# Power_grad.net
KiCad netlist of a schematic drawn in EAGLE
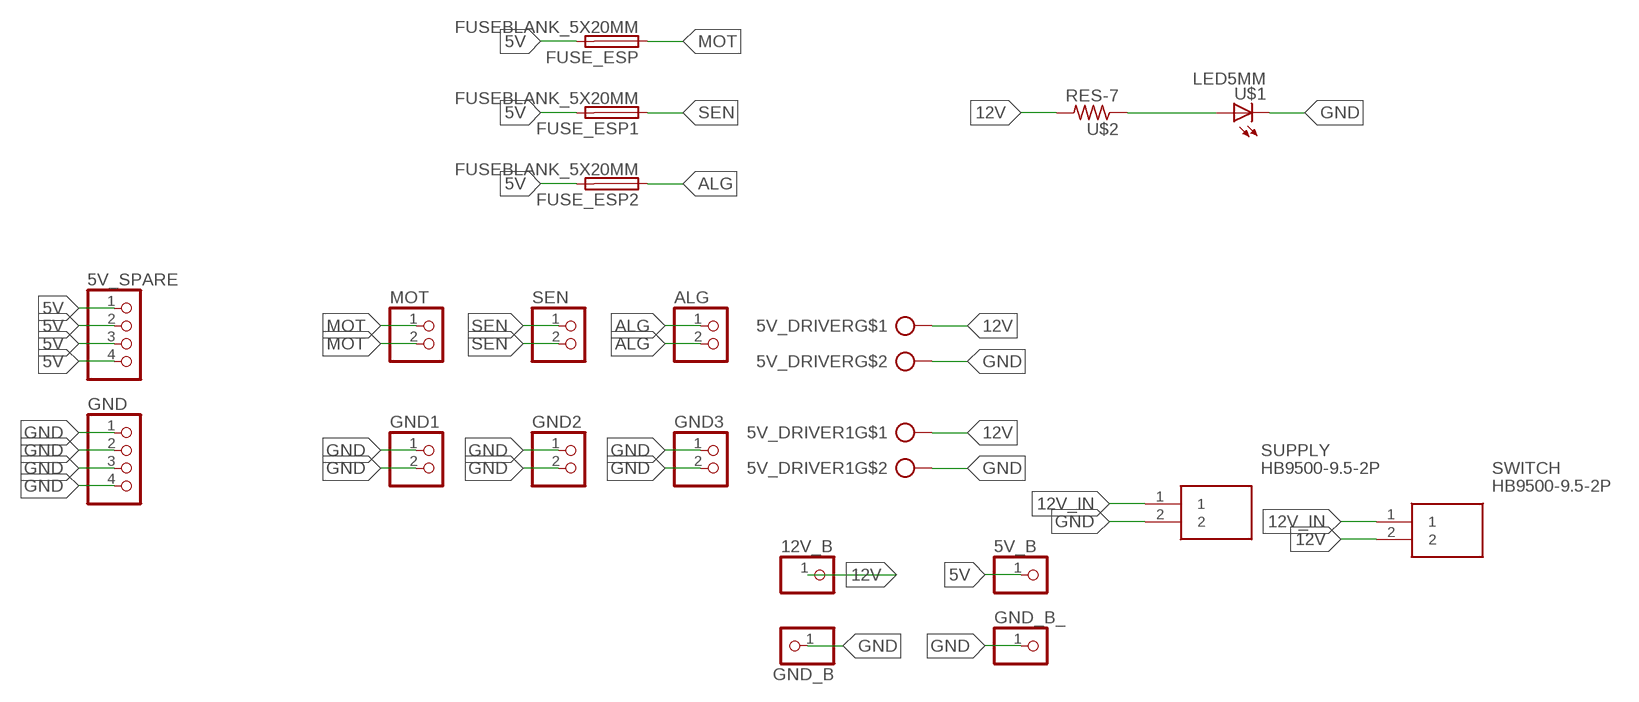
[diagram p0: schematic, sheet 1]

(export (version "E")
  (design (tool "Eeschema 10.0.6"))
  (components
    (comp (ref "5V_B")
      (value "PINHD-1X1")
      (footprint "eagle-import:1X01")
      (libsource (lib "eagle-import") (part "PINHD-1X1"))
    )
    (comp (ref "5V_DRIVER")
      (value "CON_PTR_2")
      (footprint "eagle-import:AK300_2")
      (libsource (lib "eagle-import") (part "CON_PTR_2"))
    )
    (comp (ref "5V_DRIVER1")
      (value "CON_PTR_2")
      (footprint "eagle-import:AK300_2")
      (libsource (lib "eagle-import") (part "CON_PTR_2"))
    )
    (comp (ref "5V_SPARE")
      (value "PINHD-1X4")
      (footprint "eagle-import:1X04")
      (libsource (lib "eagle-import") (part "PINHD-1X4"))
    )
    (comp (ref "12V_B")
      (value "PINHD-1X1")
      (footprint "eagle-import:1X01")
      (libsource (lib "eagle-import") (part "PINHD-1X1"))
    )
    (comp (ref "ALG")
      (value "PINHD-2_DATA")
      (footprint "eagle-import:1X02_DATA")
      (libsource (lib "eagle-import") (part "PINHD-2_DATA"))
    )
    (comp (ref "FUSE_ESP")
      (value "FUSEBLANK_5X20MM")
      (footprint "eagle-import:FUSE_HOLDER_5X20MM")
      (libsource (lib "eagle-import") (part "FUSEBLANK_5X20MM"))
    )
    (comp (ref "FUSE_ESP1")
      (value "FUSEBLANK_5X20MM")
      (footprint "eagle-import:FUSE_HOLDER_5X20MM")
      (libsource (lib "eagle-import") (part "FUSEBLANK_5X20MM"))
    )
    (comp (ref "FUSE_ESP2")
      (value "FUSEBLANK_5X20MM")
      (footprint "eagle-import:FUSE_HOLDER_5X20MM")
      (libsource (lib "eagle-import") (part "FUSEBLANK_5X20MM"))
    )
    (comp (ref "GND")
      (value "PINHD-1X4")
      (footprint "eagle-import:1X04")
      (libsource (lib "eagle-import") (part "PINHD-1X4"))
    )
    (comp (ref "GND1")
      (value "PINHD-2_DATA")
      (footprint "eagle-import:1X02_DATA")
      (libsource (lib "eagle-import") (part "PINHD-2_DATA"))
    )
    (comp (ref "GND2")
      (value "PINHD-2_DATA")
      (footprint "eagle-import:1X02_DATA")
      (libsource (lib "eagle-import") (part "PINHD-2_DATA"))
    )
    (comp (ref "GND3")
      (value "PINHD-2_DATA")
      (footprint "eagle-import:1X02_DATA")
      (libsource (lib "eagle-import") (part "PINHD-2_DATA"))
    )
    (comp (ref "GND_B")
      (value "PINHD-1X1")
      (footprint "eagle-import:1X01")
      (libsource (lib "eagle-import") (part "PINHD-1X1"))
    )
    (comp (ref "GND_B_")
      (value "PINHD-1X1")
      (footprint "eagle-import:1X01")
      (libsource (lib "eagle-import") (part "PINHD-1X1"))
    )
    (comp (ref "MOT")
      (value "PINHD-2_DATA")
      (footprint "eagle-import:1X02_DATA")
      (libsource (lib "eagle-import") (part "PINHD-2_DATA"))
    )
    (comp (ref "SEN")
      (value "PINHD-2_DATA")
      (footprint "eagle-import:1X02_DATA")
      (libsource (lib "eagle-import") (part "PINHD-2_DATA"))
    )
    (comp (ref "SUPPLY")
      (value "HB9500-9.5-2P")
      (footprint "eagle-import:SHDR2W140P0X950_1X2_2055X1800X")
      (libsource (lib "eagle-import") (part "HB9500-9.5-2P"))
    )
    (comp (ref "SWITCH")
      (value "HB9500-9.5-2P")
      (footprint "eagle-import:SHDR2W140P0X950_1X2_2055X1800X")
      (libsource (lib "eagle-import") (part "HB9500-9.5-2P"))
    )
    (comp (ref "U$1")
      (value "LED5MM")
      (footprint "eagle-import:LED5MM")
      (libsource (lib "eagle-import") (part "LED5MM"))
    )
    (comp (ref "U$2")
      (value "RES-7")
      (footprint "eagle-import:0204_7")
      (libsource (lib "eagle-import") (part "RES-7"))
    )
  )
  (nets
    (net (code "1") (name "5V") (class "Default")
      (node (ref "5V_B") (pin "1") (pinfunction "1_1") (pintype "passive"))
      (node (ref "5V_SPARE") (pin "1") (pinfunction "1_1") (pintype "passive"))
      (node (ref "5V_SPARE") (pin "2") (pinfunction "2_2") (pintype "passive"))
      (node (ref "5V_SPARE") (pin "3") (pinfunction "3_3") (pintype "passive"))
      (node (ref "5V_SPARE") (pin "4") (pinfunction "4_4") (pintype "passive"))
      (node (ref "FUSE_ESP") (pin "2") (pinfunction "2_2") (pintype "passive"))
      (node (ref "FUSE_ESP1") (pin "2") (pinfunction "2_2") (pintype "passive"))
      (node (ref "FUSE_ESP2") (pin "2") (pinfunction "2_2") (pintype "passive"))
    )
    (net (code "2") (name "12V") (class "Default")
      (node (ref "12V_B") (pin "1") (pinfunction "1_1") (pintype "passive"))
      (node (ref "5V_DRIVER") (pin "1") (pinfunction "KL_1") (pintype "passive"))
      (node (ref "5V_DRIVER1") (pin "1") (pinfunction "KL_1") (pintype "passive"))
      (node (ref "SWITCH") (pin "2") (pinfunction "2_2") (pintype "bidirectional"))
      (node (ref "U$2") (pin "2") (pinfunction "2_2") (pintype "passive"))
    )
    (net (code "3") (name "12V_IN") (class "Default")
      (node (ref "SUPPLY") (pin "1") (pinfunction "1_1") (pintype "bidirectional"))
      (node (ref "SWITCH") (pin "1") (pinfunction "1_1") (pintype "bidirectional"))
    )
    (net (code "4") (name "ALG") (class "Default")
      (node (ref "ALG") (pin "1") (pinfunction "1_1") (pintype "passive"))
      (node (ref "ALG") (pin "2") (pinfunction "2_2") (pintype "passive"))
      (node (ref "FUSE_ESP2") (pin "1") (pinfunction "1_1") (pintype "passive"))
    )
    (net (code "5") (name "GND") (class "Default")
      (node (ref "5V_DRIVER") (pin "2") (pinfunction "KL_2") (pintype "passive"))
      (node (ref "5V_DRIVER1") (pin "2") (pinfunction "KL_2") (pintype "passive"))
      (node (ref "GND") (pin "1") (pinfunction "1_1") (pintype "passive"))
      (node (ref "GND") (pin "2") (pinfunction "2_2") (pintype "passive"))
      (node (ref "GND") (pin "3") (pinfunction "3_3") (pintype "passive"))
      (node (ref "GND") (pin "4") (pinfunction "4_4") (pintype "passive"))
      (node (ref "GND1") (pin "1") (pinfunction "1_1") (pintype "passive"))
      (node (ref "GND1") (pin "2") (pinfunction "2_2") (pintype "passive"))
      (node (ref "GND2") (pin "1") (pinfunction "1_1") (pintype "passive"))
      (node (ref "GND2") (pin "2") (pinfunction "2_2") (pintype "passive"))
      (node (ref "GND3") (pin "1") (pinfunction "1_1") (pintype "passive"))
      (node (ref "GND3") (pin "2") (pinfunction "2_2") (pintype "passive"))
      (node (ref "GND_B") (pin "1") (pinfunction "1_1") (pintype "passive"))
      (node (ref "GND_B_") (pin "1") (pinfunction "1_1") (pintype "passive"))
      (node (ref "SUPPLY") (pin "2") (pinfunction "2_2") (pintype "bidirectional"))
      (node (ref "U$1") (pin "K") (pinfunction "C_K") (pintype "passive"))
    )
    (net (code "6") (name "MOT") (class "Default")
      (node (ref "FUSE_ESP") (pin "1") (pinfunction "1_1") (pintype "passive"))
      (node (ref "MOT") (pin "1") (pinfunction "1_1") (pintype "passive"))
      (node (ref "MOT") (pin "2") (pinfunction "2_2") (pintype "passive"))
    )
    (net (code "7") (name "Net-(U$1-PadA)") (class "Default")
      (node (ref "U$1") (pin "A") (pinfunction "A_A") (pintype "passive"))
      (node (ref "U$2") (pin "1") (pinfunction "1_1") (pintype "passive"))
    )
    (net (code "8") (name "SEN") (class "Default")
      (node (ref "FUSE_ESP1") (pin "1") (pinfunction "1_1") (pintype "passive"))
      (node (ref "SEN") (pin "1") (pinfunction "1_1") (pintype "passive"))
      (node (ref "SEN") (pin "2") (pinfunction "2_2") (pintype "passive"))
    )
  )
)
